# B1001_01.net
KiCad netlist of a schematic drawn in Altium Designer
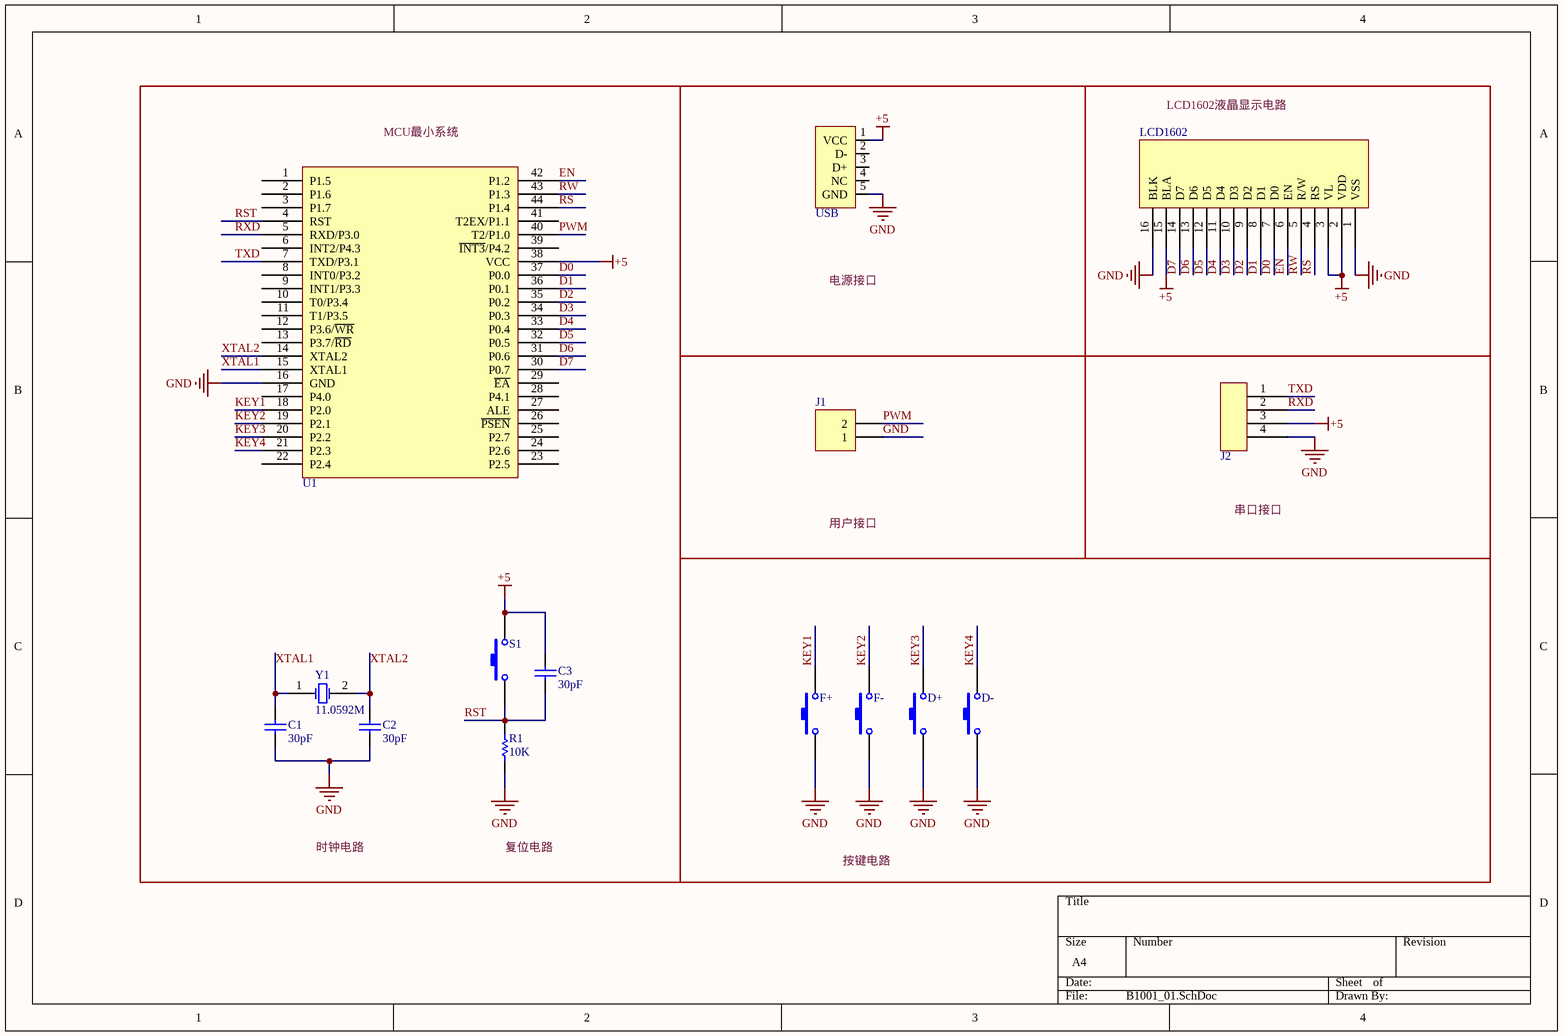
[diagram p0: B1001_01.SchDoc]

(export (version "E")
  (design (tool "Eeschema 10.0.6"))
  (components
    (comp (ref "C1")
      (value "30pF")
      (footprint "user:0603P")
      (description "Capacitor")
      (fields (field (name "Comment") "Cap") (field (name "PUBLISHER") "Altium Limited"))
      (libsource (lib "Miscellaneous Devices") (part "Cap"))
    )
    (comp (ref "C2")
      (value "30pF")
      (footprint "user:0603P")
      (description "Capacitor")
      (fields (field (name "Comment") "Cap") (field (name "PUBLISHER") "Altium Limited"))
      (libsource (lib "Miscellaneous Devices") (part "Cap"))
    )
    (comp (ref "C3")
      (value "30pF")
      (footprint "user:0603P")
      (description "Capacitor")
      (fields (field (name "Comment") "Cap") (field (name "PUBLISHER") "Altium Limited"))
      (libsource (lib "Miscellaneous Devices") (part "Cap"))
    )
    (comp (ref "D+")
      (value "SW-PB")
      (footprint "user:SMD4")
      (description "Switch")
      (fields (field (name "PUBLISHER") "Altium Limited"))
      (libsource (lib "Miscellaneous Devices") (part "SW-PB"))
    )
    (comp (ref "D-")
      (value "SW-PB")
      (footprint "user:SMD4")
      (description "Switch")
      (fields (field (name "PUBLISHER") "Altium Limited"))
      (libsource (lib "Miscellaneous Devices") (part "SW-PB"))
    )
    (comp (ref "F+")
      (value "SW-PB")
      (footprint "user:SMD4")
      (description "Switch")
      (fields (field (name "PUBLISHER") "Altium Limited"))
      (libsource (lib "Miscellaneous Devices") (part "SW-PB"))
    )
    (comp (ref "F-")
      (value "SW-PB")
      (footprint "user:SMD4")
      (description "Switch")
      (fields (field (name "PUBLISHER") "Altium Limited"))
      (libsource (lib "Miscellaneous Devices") (part "SW-PB"))
    )
    (comp (ref "J1")
      (value "Header 2")
      (footprint "HDR1X2")
      (description "Header, 2-Pin")
      (fields (field (name "PUBLISHER") "Altium Limited"))
      (libsource (lib "Miscellaneous Connectors") (part "Header 2"))
    )
    (comp (ref "J2")
      (value "CON4")
      (footprint "HDR1X4")
      (libsource (lib "altium-import") (part "root_0_CON4_"))
    )
    (comp (ref "LCD1602")
      (value "LCD1602")
      (footprint "HDR1X16")
      (libsource (lib "altium-import") (part "root_3_LCD1602_"))
    )
    (comp (ref "R1")
      (value "10K")
      (footprint "user:0603P")
      (description "Resistor")
      (fields (field (name "Comment") "Res1") (field (name "PUBLISHER") "Altium Limited"))
      (libsource (lib "Miscellaneous Devices") (part "Res1"))
    )
    (comp (ref "S1")
      (value "SW-PB")
      (footprint "user:SMD4")
      (description "Switch")
      (fields (field (name "PUBLISHER") "Altium Limited"))
      (libsource (lib "Miscellaneous Devices") (part "SW-PB"))
    )
    (comp (ref "U1")
      (value "STC89C52")
      (footprint "user:LQFP-44")
      (libsource (lib "altium-import") (part "root_0_STC89C52_"))
    )
    (comp (ref "USB")
      (value "USB")
      (footprint "user:USB/SM0.8-6H5")
      (libsource (lib "altium-import") (part "root_0_USB_"))
    )
    (comp (ref "Y1")
      (value "11.0592M")
      (footprint "user:SMD5032")
      (description "Crystal Oscillator")
      (fields (field (name "PUBLISHER") "Altium Limited"))
      (libsource (lib "Miscellaneous Devices") (part "XTAL"))
    )
  )
  (nets
    (net (code "1") (name "+5") (class "Default")
      (node (ref "C3") (pin "2") (pinfunction "2_2") (pintype "passive"))
      (node (ref "J2") (pin "3") (pinfunction "3_3") (pintype "passive"))
      (node (ref "LCD1602") (pin "15") (pinfunction "BLA_15") (pintype "passive"))
      (node (ref "LCD1602") (pin "2") (pinfunction "VDD_2") (pintype "passive"))
      (node (ref "LCD1602") (pin "3") (pinfunction "VL_3") (pintype "passive"))
      (node (ref "S1") (pin "2") (pinfunction "2_2") (pintype "passive"))
      (node (ref "U1") (pin "38") (pinfunction "VCC_38") (pintype "passive"))
      (node (ref "USB") (pin "1") (pinfunction "VCC_1") (pintype "passive"))
    )
    (net (code "2") (name "/D0") (class "Default")
      (node (ref "LCD1602") (pin "7") (pinfunction "D0_7") (pintype "passive"))
      (node (ref "U1") (pin "37") (pinfunction "P0.0_37") (pintype "passive"))
    )
    (net (code "3") (name "/D1") (class "Default")
      (node (ref "LCD1602") (pin "8") (pinfunction "D1_8") (pintype "passive"))
      (node (ref "U1") (pin "36") (pinfunction "P0.1_36") (pintype "passive"))
    )
    (net (code "4") (name "/D2") (class "Default")
      (node (ref "LCD1602") (pin "9") (pinfunction "D2_9") (pintype "passive"))
      (node (ref "U1") (pin "35") (pinfunction "P0.2_35") (pintype "passive"))
    )
    (net (code "5") (name "/D3") (class "Default")
      (node (ref "LCD1602") (pin "10") (pinfunction "D3_10") (pintype "passive"))
      (node (ref "U1") (pin "34") (pinfunction "P0.3_34") (pintype "passive"))
    )
    (net (code "6") (name "/D4") (class "Default")
      (node (ref "LCD1602") (pin "11") (pinfunction "D4_11") (pintype "passive"))
      (node (ref "U1") (pin "33") (pinfunction "P0.4_33") (pintype "passive"))
    )
    (net (code "7") (name "/D5") (class "Default")
      (node (ref "LCD1602") (pin "12") (pinfunction "D5_12") (pintype "passive"))
      (node (ref "U1") (pin "32") (pinfunction "P0.5_32") (pintype "passive"))
    )
    (net (code "8") (name "/D6") (class "Default")
      (node (ref "LCD1602") (pin "13") (pinfunction "D6_13") (pintype "passive"))
      (node (ref "U1") (pin "31") (pinfunction "P0.6_31") (pintype "passive"))
    )
    (net (code "9") (name "/D7") (class "Default")
      (node (ref "LCD1602") (pin "14") (pinfunction "D7_14") (pintype "passive"))
      (node (ref "U1") (pin "30") (pinfunction "P0.7_30") (pintype "passive"))
    )
    (net (code "10") (name "/EN") (class "Default")
      (node (ref "LCD1602") (pin "6") (pinfunction "EN_6") (pintype "passive"))
      (node (ref "U1") (pin "42") (pinfunction "P1.2_42") (pintype "passive"))
    )
    (net (code "11") (name "/KEY1") (class "Default")
      (node (ref "F+") (pin "2") (pinfunction "2_2") (pintype "passive"))
      (node (ref "U1") (pin "18") (pinfunction "P2.0_18") (pintype "passive"))
    )
    (net (code "12") (name "/KEY2") (class "Default")
      (node (ref "F-") (pin "2") (pinfunction "2_2") (pintype "passive"))
      (node (ref "U1") (pin "19") (pinfunction "P2.1_19") (pintype "passive"))
    )
    (net (code "13") (name "/KEY3") (class "Default")
      (node (ref "D+") (pin "2") (pinfunction "2_2") (pintype "passive"))
      (node (ref "U1") (pin "20") (pinfunction "P2.2_20") (pintype "passive"))
    )
    (net (code "14") (name "/KEY4") (class "Default")
      (node (ref "D-") (pin "2") (pinfunction "2_2") (pintype "passive"))
      (node (ref "U1") (pin "21") (pinfunction "P2.3_21") (pintype "passive"))
    )
    (net (code "15") (name "/PWM") (class "Default")
      (node (ref "J1") (pin "2") (pinfunction "2_2") (pintype "passive"))
      (node (ref "U1") (pin "40") (pinfunction "T2/P1.0_40") (pintype "passive"))
    )
    (net (code "16") (name "/RS") (class "Default")
      (node (ref "LCD1602") (pin "4") (pinfunction "RS_4") (pintype "passive"))
      (node (ref "U1") (pin "44") (pinfunction "P1.4_44") (pintype "passive"))
    )
    (net (code "17") (name "/RST") (class "Default")
      (node (ref "C3") (pin "1") (pinfunction "1_1") (pintype "passive"))
      (node (ref "R1") (pin "2") (pinfunction "2_2") (pintype "passive"))
      (node (ref "S1") (pin "1") (pinfunction "1_1") (pintype "passive"))
      (node (ref "U1") (pin "4") (pinfunction "RST_4") (pintype "passive"))
    )
    (net (code "18") (name "/RW") (class "Default")
      (node (ref "LCD1602") (pin "5") (pinfunction "R/W_5") (pintype "passive"))
      (node (ref "U1") (pin "43") (pinfunction "P1.3_43") (pintype "passive"))
    )
    (net (code "19") (name "/RXD") (class "Default")
      (node (ref "J2") (pin "2") (pinfunction "2_2") (pintype "passive"))
      (node (ref "U1") (pin "5") (pinfunction "RXD/P3.0_5") (pintype "passive"))
    )
    (net (code "20") (name "/TXD") (class "Default")
      (node (ref "J2") (pin "1") (pinfunction "1_1") (pintype "passive"))
      (node (ref "U1") (pin "7") (pinfunction "TXD/P3.1_7") (pintype "passive"))
    )
    (net (code "21") (name "/XTAL1") (class "Default")
      (node (ref "C1") (pin "2") (pinfunction "2_2") (pintype "passive"))
      (node (ref "U1") (pin "15") (pinfunction "XTAL1_15") (pintype "passive"))
      (node (ref "Y1") (pin "1") (pinfunction "OSC1_1") (pintype "passive"))
    )
    (net (code "22") (name "/XTAL2") (class "Default")
      (node (ref "C2") (pin "2") (pinfunction "2_2") (pintype "passive"))
      (node (ref "U1") (pin "14") (pinfunction "XTAL2_14") (pintype "passive"))
      (node (ref "Y1") (pin "2") (pinfunction "OSC2_2") (pintype "passive"))
    )
    (net (code "23") (name "GND") (class "Default")
      (node (ref "C1") (pin "1") (pinfunction "1_1") (pintype "passive"))
      (node (ref "C2") (pin "1") (pinfunction "1_1") (pintype "passive"))
      (node (ref "D+") (pin "1") (pinfunction "1_1") (pintype "passive"))
      (node (ref "D-") (pin "1") (pinfunction "1_1") (pintype "passive"))
      (node (ref "F+") (pin "1") (pinfunction "1_1") (pintype "passive"))
      (node (ref "F-") (pin "1") (pinfunction "1_1") (pintype "passive"))
      (node (ref "J1") (pin "1") (pinfunction "1_1") (pintype "passive"))
      (node (ref "J2") (pin "4") (pinfunction "4_4") (pintype "passive"))
      (node (ref "LCD1602") (pin "1") (pinfunction "VSS_1") (pintype "passive"))
      (node (ref "LCD1602") (pin "16") (pinfunction "BLK_16") (pintype "passive"))
      (node (ref "R1") (pin "1") (pinfunction "1_1") (pintype "passive"))
      (node (ref "U1") (pin "16") (pinfunction "GND_16") (pintype "passive"))
      (node (ref "USB") (pin "5") (pinfunction "GND_5") (pintype "passive"))
    )
    (net (code "24") (name "unconnected-(U1-ALE-Pad27)") (class "Default")
      (node (ref "U1") (pin "27") (pinfunction "ALE_27") (pintype "passive"))
    )
    (net (code "25") (name "unconnected-(U1-INT0{slash}P3.2-Pad8)") (class "Default")
      (node (ref "U1") (pin "8") (pinfunction "INT0/P3.2_8") (pintype "passive"))
    )
    (net (code "26") (name "unconnected-(U1-INT1{slash}P3.3-Pad9)") (class "Default")
      (node (ref "U1") (pin "9") (pinfunction "INT1/P3.3_9") (pintype "passive"))
    )
    (net (code "27") (name "unconnected-(U1-INT2{slash}P4.3-Pad6)") (class "Default")
      (node (ref "U1") (pin "6") (pinfunction "INT2/P4.3_6") (pintype "passive"))
    )
    (net (code "28") (name "unconnected-(U1-P1.5-Pad1)") (class "Default")
      (node (ref "U1") (pin "1") (pinfunction "P1.5_1") (pintype "passive"))
    )
    (net (code "29") (name "unconnected-(U1-P1.6-Pad2)") (class "Default")
      (node (ref "U1") (pin "2") (pinfunction "P1.6_2") (pintype "passive"))
    )
    (net (code "30") (name "unconnected-(U1-P1.7-Pad3)") (class "Default")
      (node (ref "U1") (pin "3") (pinfunction "P1.7_3") (pintype "passive"))
    )
    (net (code "31") (name "unconnected-(U1-P2.4-Pad22)") (class "Default")
      (node (ref "U1") (pin "22") (pinfunction "P2.4_22") (pintype "passive"))
    )
    (net (code "32") (name "unconnected-(U1-P2.5-Pad23)") (class "Default")
      (node (ref "U1") (pin "23") (pinfunction "P2.5_23") (pintype "passive"))
    )
    (net (code "33") (name "unconnected-(U1-P2.6-Pad24)") (class "Default")
      (node (ref "U1") (pin "24") (pinfunction "P2.6_24") (pintype "passive"))
    )
    (net (code "34") (name "unconnected-(U1-P2.7-Pad25)") (class "Default")
      (node (ref "U1") (pin "25") (pinfunction "P2.7_25") (pintype "passive"))
    )
    (net (code "35") (name "unconnected-(U1-P3.6{slash}~{WR}-Pad12)") (class "Default")
      (node (ref "U1") (pin "12") (pinfunction "P3.6/~{WR}_12") (pintype "passive"))
    )
    (net (code "36") (name "unconnected-(U1-P3.7{slash}~{RD}-Pad13)") (class "Default")
      (node (ref "U1") (pin "13") (pinfunction "P3.7/~{RD}_13") (pintype "passive"))
    )
    (net (code "37") (name "unconnected-(U1-P4.0-Pad17)") (class "Default")
      (node (ref "U1") (pin "17") (pinfunction "P4.0_17") (pintype "passive"))
    )
    (net (code "38") (name "unconnected-(U1-P4.1-Pad28)") (class "Default")
      (node (ref "U1") (pin "28") (pinfunction "P4.1_28") (pintype "passive"))
    )
    (net (code "39") (name "unconnected-(U1-T0{slash}P3.4-Pad10)") (class "Default")
      (node (ref "U1") (pin "10") (pinfunction "T0/P3.4_10") (pintype "passive"))
    )
    (net (code "40") (name "unconnected-(U1-T1{slash}P3.5-Pad11)") (class "Default")
      (node (ref "U1") (pin "11") (pinfunction "T1/P3.5_11") (pintype "passive"))
    )
    (net (code "41") (name "unconnected-(U1-T2EX{slash}P1.1-Pad41)") (class "Default")
      (node (ref "U1") (pin "41") (pinfunction "T2EX/P1.1_41") (pintype "passive"))
    )
    (net (code "42") (name "unconnected-(U1-~{EA}-Pad29)") (class "Default")
      (node (ref "U1") (pin "29") (pinfunction "~{EA}_29") (pintype "passive"))
    )
    (net (code "43") (name "unconnected-(U1-~{INT3}{slash}P4.2-Pad39)") (class "Default")
      (node (ref "U1") (pin "39") (pinfunction "~{INT3}/P4.2_39") (pintype "passive"))
    )
    (net (code "44") (name "unconnected-(U1-~{PSEN}-Pad26)") (class "Default")
      (node (ref "U1") (pin "26") (pinfunction "~{PSEN}_26") (pintype "passive"))
    )
    (net (code "45") (name "unconnected-(USB-D+-Pad3)") (class "Default")
      (node (ref "USB") (pin "3") (pinfunction "D+_3") (pintype "passive"))
    )
    (net (code "46") (name "unconnected-(USB-D--Pad2)") (class "Default")
      (node (ref "USB") (pin "2") (pinfunction "D-_2") (pintype "passive"))
    )
    (net (code "47") (name "unconnected-(USB-NC-Pad4)") (class "Default")
      (node (ref "USB") (pin "4") (pinfunction "NC_4") (pintype "passive"))
    )
  )
)
